# subtracter.net
KiCad netlist of a schematic drawn in Altium Designer
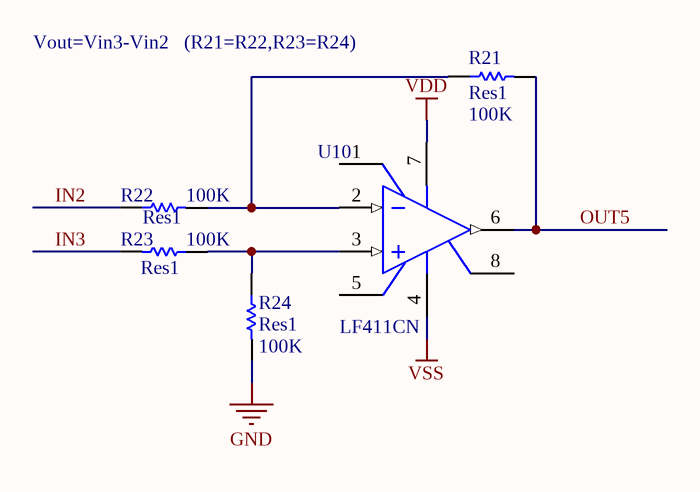
[diagram p0: subtracter.SchDoc]

(export (version "E")
  (design (tool "Eeschema 10.0.6"))
  (components
    (comp (ref "R21")
      (value "Res1")
      (footprint "AXIAL-0.3")
      (description "Resistor")
      (fields (field (name "ALTIUM_VALUE") "100K") (field (name "PUBLISHER") "Altium Limited"))
      (libsource (lib "Miscellaneous Devices") (part "Res1"))
    )
    (comp (ref "R22")
      (value "Res1")
      (footprint "AXIAL-0.3")
      (description "Resistor")
      (fields (field (name "ALTIUM_VALUE") "100K") (field (name "PUBLISHER") "Altium Limited"))
      (libsource (lib "Miscellaneous Devices") (part "Res1"))
    )
    (comp (ref "R23")
      (value "Res1")
      (footprint "AXIAL-0.3")
      (description "Resistor")
      (fields (field (name "ALTIUM_VALUE") "100K") (field (name "PUBLISHER") "Altium Limited"))
      (libsource (lib "Miscellaneous Devices") (part "Res1"))
    )
    (comp (ref "R24")
      (value "Res1")
      (footprint "AXIAL-0.3")
      (description "Resistor")
      (fields (field (name "ALTIUM_VALUE") "100K") (field (name "PUBLISHER") "Altium Limited"))
      (libsource (lib "Miscellaneous Devices") (part "Res1"))
    )
    (comp (ref "U10")
      (value "LF411CN")
      (footprint "N08E")
      (description "Low Offset, Low Drift JFET Input Operational Amplifier, 8-pin MDIP")
      (fields
        (field (name "MANUFACTURER") "National Semiconductor")
        (field (name "PUBLISHER") "Altium Limited")
      )
      (libsource (lib "NSC Amplifier") (part "LF411CN"))
    )
  )
  (nets
    (net (code "1") (name "/IN2") (class "Default")
      (node (ref "R22") (pin "1") (pinfunction "1_1") (pintype "passive"))
    )
    (net (code "2") (name "/IN3") (class "Default")
      (node (ref "R23") (pin "2") (pinfunction "2_2") (pintype "passive"))
    )
    (net (code "3") (name "/OUT5") (class "Default")
      (node (ref "R21") (pin "2") (pinfunction "2_2") (pintype "passive"))
      (node (ref "U10") (pin "6") (pinfunction "OUT_6") (pintype "output"))
    )
    (net (code "4") (name "GND") (class "Default")
      (node (ref "R24") (pin "2") (pinfunction "2_2") (pintype "passive"))
    )
    (net (code "5") (name "Net-(U10-IN+)") (class "Default")
      (node (ref "R23") (pin "1") (pinfunction "1_1") (pintype "passive"))
      (node (ref "R24") (pin "1") (pinfunction "1_1") (pintype "passive"))
      (node (ref "U10") (pin "3") (pinfunction "IN+_3") (pintype "input"))
    )
    (net (code "6") (name "Net-(U10-IN-)") (class "Default")
      (node (ref "R21") (pin "1") (pinfunction "1_1") (pintype "passive"))
      (node (ref "R22") (pin "2") (pinfunction "2_2") (pintype "passive"))
      (node (ref "U10") (pin "2") (pinfunction "IN-_2") (pintype "input"))
    )
    (net (code "7") (name "VDD") (class "Default")
      (node (ref "U10") (pin "7") (pinfunction "V+_7") (pintype "power_in"))
    )
    (net (code "8") (name "VSS") (class "Default")
      (node (ref "U10") (pin "4") (pinfunction "V-_4") (pintype "power_in"))
    )
    (net (code "9") (name "unconnected-(U10-BAL-Pad1)") (class "Default")
      (node (ref "U10") (pin "1") (pinfunction "BAL_1") (pintype "passive"))
    )
    (net (code "10") (name "unconnected-(U10-BAL-Pad5)") (class "Default")
      (node (ref "U10") (pin "5") (pinfunction "BAL_5") (pintype "passive"))
    )
    (net (code "11") (name "unconnected-(U10-NC-Pad8)") (class "Default")
      (node (ref "U10") (pin "8") (pinfunction "NC_8") (pintype "passive"))
    )
  )
)
